# ADS1299.net
KiCad netlist of a schematic drawn in Altium Designer
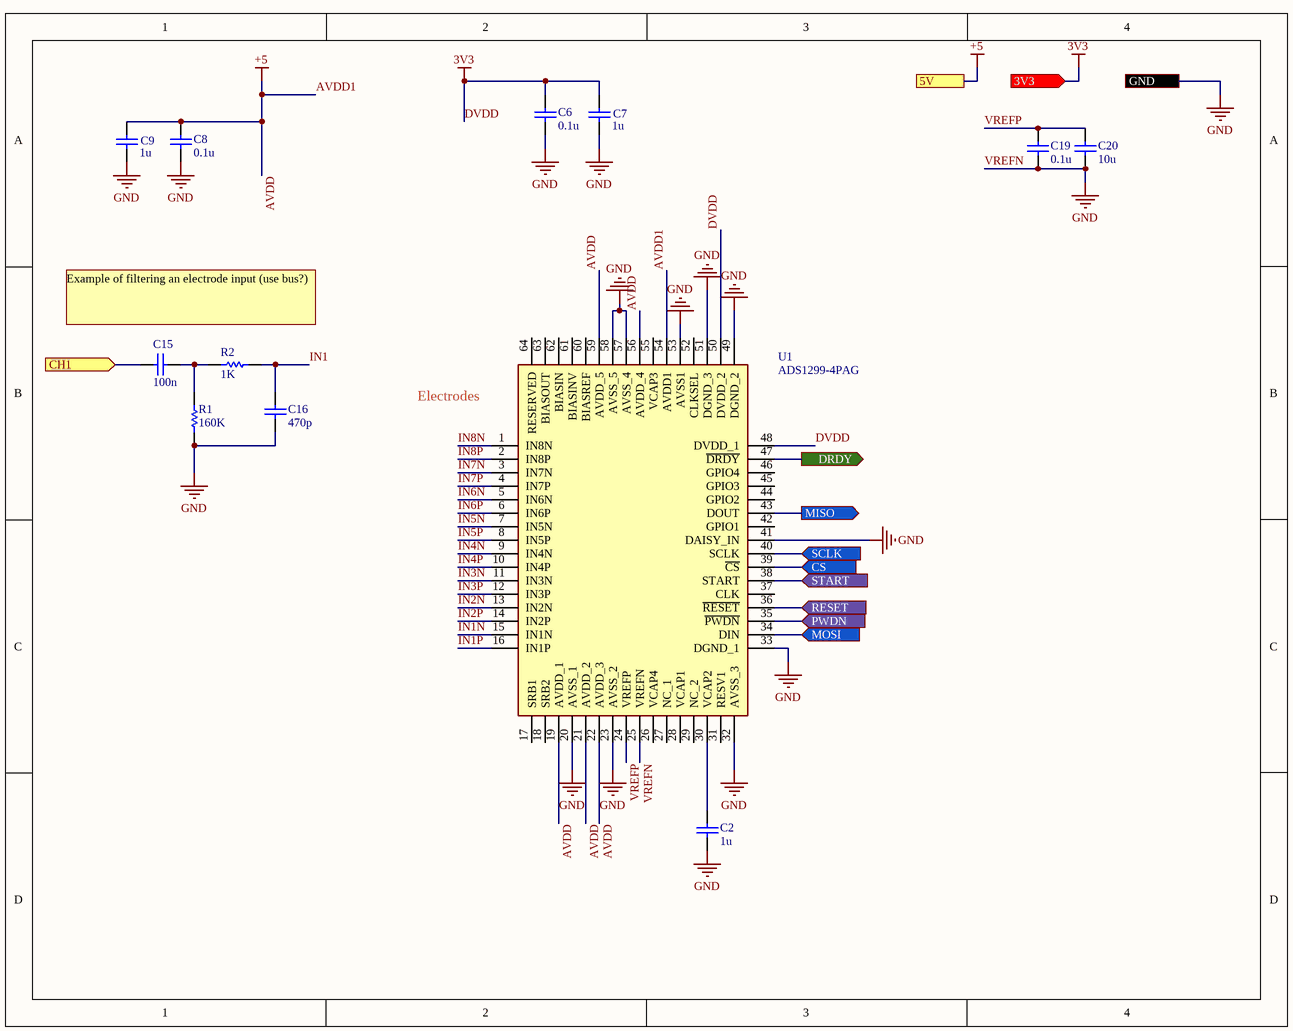
[diagram p0: ADS1299.SchDoc]

(export (version "E")
  (design (tool "Eeschema 10.0.6"))
  (components
    (comp (ref "C2")
      (value "1u")
      (description "Capacitor")
      (libsource (lib "Simulation Generic Components") (part "Capacitor"))
    )
    (comp (ref "C6")
      (value "0.1u")
      (description "Capacitor")
      (libsource (lib "Simulation Generic Components") (part "Capacitor"))
    )
    (comp (ref "C7")
      (value "1u")
      (description "Capacitor")
      (libsource (lib "Simulation Generic Components") (part "Capacitor"))
    )
    (comp (ref "C8")
      (value "0.1u")
      (description "Capacitor")
      (libsource (lib "Simulation Generic Components") (part "Capacitor"))
    )
    (comp (ref "C9")
      (value "1u")
      (description "Capacitor")
      (libsource (lib "Simulation Generic Components") (part "Capacitor"))
    )
    (comp (ref "C15")
      (value "100n")
      (description "Capacitor")
      (libsource (lib "Simulation Generic Components") (part "Capacitor"))
    )
    (comp (ref "C16")
      (value "470p")
      (description "Capacitor")
      (libsource (lib "Simulation Generic Components") (part "Capacitor"))
    )
    (comp (ref "C19")
      (value "0.1u")
      (description "Capacitor")
      (libsource (lib "Simulation Generic Components") (part "Capacitor"))
    )
    (comp (ref "C20")
      (value "10u")
      (description "Capacitor")
      (libsource (lib "Simulation Generic Components") (part "Capacitor"))
    )
    (comp (ref "R1")
      (value "160K")
      (description "Resistor")
      (libsource (lib "Simulation Generic Components") (part "Resistor"))
    )
    (comp (ref "R2")
      (value "1K")
      (description "Resistor")
      (libsource (lib "Simulation Generic Components") (part "Resistor"))
    )
    (comp (ref "U1")
      (value "ADS1299-4PAG")
      (footprint "QFP50P1200X1200X120-64N")
      (description "Low-Noise, 4-Channel, 24-Bit Analog-to-Digital Converter for Biopotential Measurements")
      (fields (field (name "MOUSER PART NUMBER") "595-ADS1299-4PAG"))
      (libsource (lib "ADS1299-4PAG") (part "ADS1299-4PAG"))
    )
  )
  (nets
    (net (code "1") (name "+5") (class "Default")
      (node (ref "C8") (pin "2") (pinfunction "2_2") (pintype "passive"))
      (node (ref "C9") (pin "2") (pinfunction "2_2") (pintype "passive"))
      (node (ref "U1") (pin "19") (pinfunction "AVDD_1_19") (pintype "passive"))
      (node (ref "U1") (pin "21") (pinfunction "AVDD_2_21") (pintype "passive"))
      (node (ref "U1") (pin "22") (pinfunction "AVDD_3_22") (pintype "passive"))
      (node (ref "U1") (pin "54") (pinfunction "AVDD1_54") (pintype "passive"))
      (node (ref "U1") (pin "56") (pinfunction "AVDD_4_56") (pintype "passive"))
      (node (ref "U1") (pin "59") (pinfunction "AVDD_5_59") (pintype "passive"))
    )
    (net (code "2") (name "/CH1") (class "Default")
      (node (ref "C15") (pin "2") (pinfunction "2_2") (pintype "passive"))
    )
    (net (code "3") (name "/CS") (class "Default")
      (node (ref "U1") (pin "39") (pinfunction "~{CS}_39") (pintype "passive"))
    )
    (net (code "4") (name "/DRDY") (class "Default")
      (node (ref "U1") (pin "47") (pinfunction "~{DRDY}_47") (pintype "passive"))
    )
    (net (code "5") (name "/IN1") (class "Default")
      (node (ref "C16") (pin "2") (pinfunction "2_2") (pintype "passive"))
      (node (ref "R2") (pin "2") (pinfunction "2_2") (pintype "passive"))
    )
    (net (code "6") (name "/IN1N") (class "Default")
      (node (ref "U1") (pin "15") (pinfunction "IN1N_15") (pintype "passive"))
    )
    (net (code "7") (name "/IN1P") (class "Default")
      (node (ref "U1") (pin "16") (pinfunction "IN1P_16") (pintype "passive"))
    )
    (net (code "8") (name "/IN2N") (class "Default")
      (node (ref "U1") (pin "13") (pinfunction "IN2N_13") (pintype "passive"))
    )
    (net (code "9") (name "/IN2P") (class "Default")
      (node (ref "U1") (pin "14") (pinfunction "IN2P_14") (pintype "passive"))
    )
    (net (code "10") (name "/IN3N") (class "Default")
      (node (ref "U1") (pin "11") (pinfunction "IN3N_11") (pintype "passive"))
    )
    (net (code "11") (name "/IN3P") (class "Default")
      (node (ref "U1") (pin "12") (pinfunction "IN3P_12") (pintype "passive"))
    )
    (net (code "12") (name "/IN4N") (class "Default")
      (node (ref "U1") (pin "9") (pinfunction "IN4N_9") (pintype "passive"))
    )
    (net (code "13") (name "/IN4P") (class "Default")
      (node (ref "U1") (pin "10") (pinfunction "IN4P_10") (pintype "passive"))
    )
    (net (code "14") (name "/IN5N") (class "Default")
      (node (ref "U1") (pin "7") (pinfunction "IN5N_7") (pintype "passive"))
    )
    (net (code "15") (name "/IN5P") (class "Default")
      (node (ref "U1") (pin "8") (pinfunction "IN5P_8") (pintype "passive"))
    )
    (net (code "16") (name "/IN6N") (class "Default")
      (node (ref "U1") (pin "5") (pinfunction "IN6N_5") (pintype "passive"))
    )
    (net (code "17") (name "/IN6P") (class "Default")
      (node (ref "U1") (pin "6") (pinfunction "IN6P_6") (pintype "passive"))
    )
    (net (code "18") (name "/IN7N") (class "Default")
      (node (ref "U1") (pin "3") (pinfunction "IN7N_3") (pintype "passive"))
    )
    (net (code "19") (name "/IN7P") (class "Default")
      (node (ref "U1") (pin "4") (pinfunction "IN7P_4") (pintype "passive"))
    )
    (net (code "20") (name "/IN8N") (class "Default")
      (node (ref "U1") (pin "1") (pinfunction "IN8N_1") (pintype "passive"))
    )
    (net (code "21") (name "/IN8P") (class "Default")
      (node (ref "U1") (pin "2") (pinfunction "IN8P_2") (pintype "passive"))
    )
    (net (code "22") (name "/MISO") (class "Default")
      (node (ref "U1") (pin "43") (pinfunction "DOUT_43") (pintype "passive"))
    )
    (net (code "23") (name "/MOSI") (class "Default")
      (node (ref "U1") (pin "34") (pinfunction "DIN_34") (pintype "passive"))
    )
    (net (code "24") (name "/PWDN") (class "Default")
      (node (ref "U1") (pin "35") (pinfunction "~{PWDN}_35") (pintype "passive"))
    )
    (net (code "25") (name "/RESET") (class "Default")
      (node (ref "U1") (pin "36") (pinfunction "~{RESET}_36") (pintype "passive"))
    )
    (net (code "26") (name "/SCLK") (class "Default")
      (node (ref "U1") (pin "40") (pinfunction "SCLK_40") (pintype "passive"))
    )
    (net (code "27") (name "/START") (class "Default")
      (node (ref "U1") (pin "38") (pinfunction "START_38") (pintype "passive"))
    )
    (net (code "28") (name "/VREFP") (class "Default")
      (node (ref "C19") (pin "2") (pinfunction "2_2") (pintype "passive"))
      (node (ref "C20") (pin "2") (pinfunction "2_2") (pintype "passive"))
      (node (ref "U1") (pin "24") (pinfunction "VREFP_24") (pintype "passive"))
    )
    (net (code "29") (name "3V3") (class "Default")
      (node (ref "C6") (pin "2") (pinfunction "2_2") (pintype "passive"))
      (node (ref "C7") (pin "2") (pinfunction "2_2") (pintype "passive"))
      (node (ref "U1") (pin "48") (pinfunction "DVDD_1_48") (pintype "passive"))
      (node (ref "U1") (pin "50") (pinfunction "DVDD_2_50") (pintype "passive"))
    )
    (net (code "30") (name "GND") (class "Default")
      (node (ref "C16") (pin "1") (pinfunction "1_1") (pintype "passive"))
      (node (ref "C19") (pin "1") (pinfunction "1_1") (pintype "passive"))
      (node (ref "C2") (pin "2") (pinfunction "2_2") (pintype "passive"))
      (node (ref "C20") (pin "1") (pinfunction "1_1") (pintype "passive"))
      (node (ref "C6") (pin "1") (pinfunction "1_1") (pintype "passive"))
      (node (ref "C7") (pin "1") (pinfunction "1_1") (pintype "passive"))
      (node (ref "C8") (pin "1") (pinfunction "1_1") (pintype "passive"))
      (node (ref "C9") (pin "1") (pinfunction "1_1") (pintype "passive"))
      (node (ref "R1") (pin "1") (pinfunction "1_1") (pintype "passive"))
      (node (ref "U1") (pin "20") (pinfunction "AVSS_1_20") (pintype "passive"))
      (node (ref "U1") (pin "23") (pinfunction "AVSS_2_23") (pintype "passive"))
      (node (ref "U1") (pin "25") (pinfunction "VREFN_25") (pintype "passive"))
      (node (ref "U1") (pin "32") (pinfunction "AVSS_3_32") (pintype "passive"))
      (node (ref "U1") (pin "33") (pinfunction "DGND_1_33") (pintype "passive"))
      (node (ref "U1") (pin "41") (pinfunction "DAISY_IN_41") (pintype "passive"))
      (node (ref "U1") (pin "49") (pinfunction "DGND_2_49") (pintype "passive"))
      (node (ref "U1") (pin "51") (pinfunction "DGND_3_51") (pintype "passive"))
      (node (ref "U1") (pin "53") (pinfunction "AVSS1_53") (pintype "passive"))
      (node (ref "U1") (pin "57") (pinfunction "AVSS_4_57") (pintype "passive"))
      (node (ref "U1") (pin "58") (pinfunction "AVSS_5_58") (pintype "passive"))
    )
    (net (code "31") (name "Net-(C15-Pad1)") (class "Default")
      (node (ref "C15") (pin "1") (pinfunction "1_1") (pintype "passive"))
      (node (ref "R1") (pin "2") (pinfunction "2_2") (pintype "passive"))
      (node (ref "R2") (pin "1") (pinfunction "1_1") (pintype "passive"))
    )
    (net (code "32") (name "Net-(U1-VCAP2)") (class "Default")
      (node (ref "C2") (pin "1") (pinfunction "1_1") (pintype "passive"))
      (node (ref "U1") (pin "30") (pinfunction "VCAP2_30") (pintype "passive"))
    )
    (net (code "33") (name "unconnected-(U1-BIASIN-Pad62)") (class "Default")
      (node (ref "U1") (pin "62") (pinfunction "BIASIN_62") (pintype "passive"))
    )
    (net (code "34") (name "unconnected-(U1-BIASINV-Pad61)") (class "Default")
      (node (ref "U1") (pin "61") (pinfunction "BIASINV_61") (pintype "passive"))
    )
    (net (code "35") (name "unconnected-(U1-BIASOUT-Pad63)") (class "Default")
      (node (ref "U1") (pin "63") (pinfunction "BIASOUT_63") (pintype "passive"))
    )
    (net (code "36") (name "unconnected-(U1-BIASREF-Pad60)") (class "Default")
      (node (ref "U1") (pin "60") (pinfunction "BIASREF_60") (pintype "passive"))
    )
    (net (code "37") (name "unconnected-(U1-CLK-Pad37)") (class "Default")
      (node (ref "U1") (pin "37") (pinfunction "CLK_37") (pintype "passive"))
    )
    (net (code "38") (name "unconnected-(U1-CLKSEL-Pad52)") (class "Default")
      (node (ref "U1") (pin "52") (pinfunction "CLKSEL_52") (pintype "passive"))
    )
    (net (code "39") (name "unconnected-(U1-GPIO1-Pad42)") (class "Default")
      (node (ref "U1") (pin "42") (pinfunction "GPIO1_42") (pintype "passive"))
    )
    (net (code "40") (name "unconnected-(U1-GPIO2-Pad44)") (class "Default")
      (node (ref "U1") (pin "44") (pinfunction "GPIO2_44") (pintype "passive"))
    )
    (net (code "41") (name "unconnected-(U1-GPIO3-Pad45)") (class "Default")
      (node (ref "U1") (pin "45") (pinfunction "GPIO3_45") (pintype "passive"))
    )
    (net (code "42") (name "unconnected-(U1-GPIO4-Pad46)") (class "Default")
      (node (ref "U1") (pin "46") (pinfunction "GPIO4_46") (pintype "passive"))
    )
    (net (code "43") (name "unconnected-(U1-NC_1-Pad27)") (class "Default")
      (node (ref "U1") (pin "27") (pinfunction "NC_1_27") (pintype "passive"))
    )
    (net (code "44") (name "unconnected-(U1-NC_2-Pad29)") (class "Default")
      (node (ref "U1") (pin "29") (pinfunction "NC_2_29") (pintype "passive"))
    )
    (net (code "45") (name "unconnected-(U1-RESERVED-Pad64)") (class "Default")
      (node (ref "U1") (pin "64") (pinfunction "RESERVED_64") (pintype "passive"))
    )
    (net (code "46") (name "unconnected-(U1-RESV1-Pad31)") (class "Default")
      (node (ref "U1") (pin "31") (pinfunction "RESV1_31") (pintype "passive"))
    )
    (net (code "47") (name "unconnected-(U1-SRB1-Pad17)") (class "Default")
      (node (ref "U1") (pin "17") (pinfunction "SRB1_17") (pintype "passive"))
    )
    (net (code "48") (name "unconnected-(U1-SRB2-Pad18)") (class "Default")
      (node (ref "U1") (pin "18") (pinfunction "SRB2_18") (pintype "passive"))
    )
    (net (code "49") (name "unconnected-(U1-VCAP1-Pad28)") (class "Default")
      (node (ref "U1") (pin "28") (pinfunction "VCAP1_28") (pintype "passive"))
    )
    (net (code "50") (name "unconnected-(U1-VCAP3-Pad55)") (class "Default")
      (node (ref "U1") (pin "55") (pinfunction "VCAP3_55") (pintype "passive"))
    )
    (net (code "51") (name "unconnected-(U1-VCAP4-Pad26)") (class "Default")
      (node (ref "U1") (pin "26") (pinfunction "VCAP4_26") (pintype "passive"))
    )
  )
)
